# shematic.net
KiCad netlist of a schematic drawn in Altium Designer
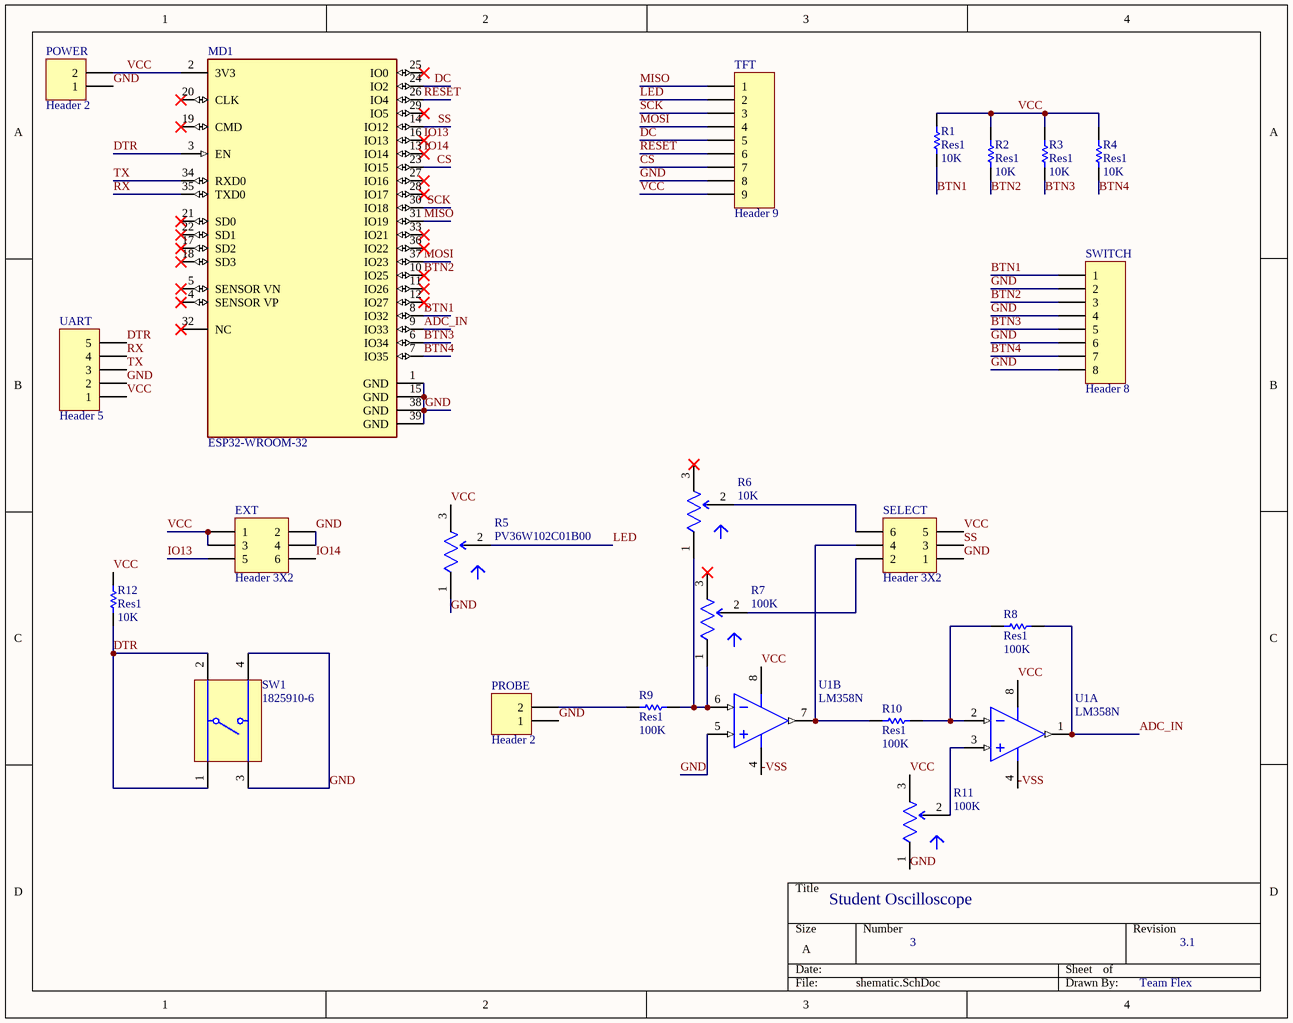
[diagram p0: shematic.SchDoc]

(export (version "E")
  (design (tool "Eeschema 10.0.6"))
  (components
    (comp (ref "EXT")
      (value "Header 3X2")
      (footprint "HDR2X3")
      (description "Header, 3-Pin, Dual row")
      (fields (field (name "PUBLISHER") "Altium Limited"))
      (libsource (lib "Miscellaneous Connectors") (part "Header 3X2"))
    )
    (comp (ref "MD1")
      (value "ESP32-WROOM-32")
      (footprint "FP-ESP32-WROOM-32-MFG")
      (description "RX TXRX MOD WIFI SURFACE MOUNT")
      (libsource (lib "Altium Content Vault") (part "ee866abf0b6c51247b7f5cdebf2f250"))
    )
    (comp (ref "POWER")
      (value "Header 2")
      (footprint "HDR1X2")
      (description "Header, 2-Pin")
      (fields (field (name "PUBLISHER") "Altium Limited"))
      (libsource (lib "Miscellaneous Connectors") (part "Header 2"))
    )
    (comp (ref "PROBE")
      (value "Header 2")
      (footprint "HDR1X2")
      (description "Header, 2-Pin")
      (fields (field (name "PUBLISHER") "Altium Limited"))
      (libsource (lib "Miscellaneous Connectors") (part "Header 2"))
    )
    (comp (ref "R1")
      (value "Res1")
      (footprint "AXIAL-0.3")
      (description "Resistor")
      (fields (field (name "ALTIUM_VALUE") "10K") (field (name "PUBLISHER") "Altium Limited"))
      (libsource (lib "Miscellaneous Devices") (part "Res1"))
    )
    (comp (ref "R2")
      (value "Res1")
      (footprint "AXIAL-0.3")
      (description "Resistor")
      (fields (field (name "ALTIUM_VALUE") "10K") (field (name "PUBLISHER") "Altium Limited"))
      (libsource (lib "Miscellaneous Devices") (part "Res1"))
    )
    (comp (ref "R3")
      (value "Res1")
      (footprint "AXIAL-0.3")
      (description "Resistor")
      (fields (field (name "ALTIUM_VALUE") "10K") (field (name "PUBLISHER") "Altium Limited"))
      (libsource (lib "Miscellaneous Devices") (part "Res1"))
    )
    (comp (ref "R4")
      (value "Res1")
      (footprint "AXIAL-0.3")
      (description "Resistor")
      (fields (field (name "ALTIUM_VALUE") "10K") (field (name "PUBLISHER") "Altium Limited"))
      (libsource (lib "Miscellaneous Devices") (part "Res1"))
    )
    (comp (ref "R5")
      (value "PV36W102C01B00")
      (footprint "FP-PV36W-MFG")
      (description "TRIMMER 1K OHM 0.5W PC PIN TOP")
      (fields
        (field (name "OCTOPART") "https://octopart.com/pv36w102c01b00-bourns-71612321")
        (field (name "TOLERANCE") "10%")
      )
      (libsource (lib "Altium Content Vault") (part "3b5a993e1b8b55ba5d1e0805a406c64"))
    )
    (comp (ref "R6")
      (value "10K")
      (footprint "FP-PV36W-MFG")
      (description "TRIMMER 1K OHM 0.5W PC PIN TOP")
      (fields
        (field (name "OCTOPART") "https://octopart.com/pv36w102c01b00-bourns-71612321")
        (field (name "MANUFACTURER PART NUMBER") "PV36W102C01B00")
      )
      (libsource (lib "Altium Content Vault") (part "3b5a993e1b8b55ba5d1e0805a406c64"))
    )
    (comp (ref "R7")
      (value "100K")
      (footprint "FP-PV36W-MFG")
      (description "TRIMMER 1K OHM 0.5W PC PIN TOP")
      (fields
        (field (name "OCTOPART") "https://octopart.com/pv36w102c01b00-bourns-71612321")
        (field (name "MANUFACTURER PART NUMBER") "PV36W102C01B00")
      )
      (libsource (lib "Altium Content Vault") (part "3b5a993e1b8b55ba5d1e0805a406c64"))
    )
    (comp (ref "R8")
      (value "Res1")
      (footprint "AXIAL-0.3")
      (description "Resistor")
      (fields (field (name "ALTIUM_VALUE") "100K") (field (name "PUBLISHER") "Altium Limited"))
      (libsource (lib "Miscellaneous Devices") (part "Res1"))
    )
    (comp (ref "R9")
      (value "Res1")
      (footprint "AXIAL-0.3")
      (description "Resistor")
      (fields (field (name "ALTIUM_VALUE") "100K") (field (name "PUBLISHER") "Altium Limited"))
      (libsource (lib "Miscellaneous Devices") (part "Res1"))
    )
    (comp (ref "R10")
      (value "Res1")
      (footprint "AXIAL-0.3")
      (description "Resistor")
      (fields (field (name "ALTIUM_VALUE") "100K") (field (name "PUBLISHER") "Altium Limited"))
      (libsource (lib "Miscellaneous Devices") (part "Res1"))
    )
    (comp (ref "R11")
      (value "100K")
      (footprint "FP-PV36W-MFG")
      (description "TRIMMER 1K OHM 0.5W PC PIN TOP")
      (fields
        (field (name "OCTOPART") "https://octopart.com/pv36w102c01b00-bourns-71612321")
        (field (name "MANUFACTURER PART NUMBER") "PV36W102C01B00")
      )
      (libsource (lib "Altium Content Vault") (part "3b5a993e1b8b55ba5d1e0805a406c64"))
    )
    (comp (ref "R12")
      (value "Res1")
      (footprint "AXIAL-0.3")
      (description "Resistor")
      (fields (field (name "ALTIUM_VALUE") "10K") (field (name "PUBLISHER") "Altium Limited"))
      (libsource (lib "Miscellaneous Devices") (part "Res1"))
    )
    (comp (ref "SELECT")
      (value "Header 3X2")
      (footprint "HDR2X3")
      (description "Header, 3-Pin, Dual row")
      (fields (field (name "PUBLISHER") "Altium Limited"))
      (libsource (lib "") (part "Header 3X2_1"))
    )
    (comp (ref "SW1")
      (value "1825910-6")
      (footprint "TECO-1825910-6_V")
      (description "Tact Switch, SPST-NO, 0.05 A, -35 to 85 degC, 4-Pin THD, RoHS, Bulk")
      (fields (field (name "MANUFACTURER") "TE Connectivity"))
      (libsource (lib "Altium Content Vault") (part "SW-SPST-4_A"))
    )
    (comp (ref "SWITCH")
      (value "Header 8")
      (footprint "HDR1X8")
      (description "Header, 8-Pin")
      (fields (field (name "PUBLISHER") "Altium Limited"))
      (libsource (lib "Miscellaneous Connectors") (part "Header 8"))
    )
    (comp (ref "TFT")
      (value "Header 9")
      (footprint "HDR1X9")
      (description "Header, 9-Pin")
      (fields (field (name "PUBLISHER") "Altium Limited"))
      (libsource (lib "Miscellaneous Connectors") (part "Header 9"))
    )
    (comp (ref "U1")
      (value "LM358N")
      (footprint "ONSC-PDIP-8-626-05_M")
      (description "Single Supply Dual Operational Amplifier, 3 to 32 V, 0 to 70 degC, 8-Pin PDIP, Tube")
      (fields (field (name "MANUFACTURER") "On Semiconductor"))
      (libsource (lib "Altium Content Vault") (part "ONSC-LM358_NCV2904-8"))
    )
    (comp (ref "UART")
      (value "Header 5")
      (footprint "HDR1X5")
      (description "Header, 5-Pin")
      (fields (field (name "PUBLISHER") "Altium Limited"))
      (libsource (lib "Miscellaneous Connectors") (part "Header 5"))
    )
  )
  (nets
    (net (code "1") (name "/-VSS") (class "Default")
      (node (ref "U1") (pin "4") (pinfunction "VEE/GND_4") (pintype "power_in"))
    )
    (net (code "2") (name "/ADC_IN") (class "Default")
      (node (ref "MD1") (pin "9") (pinfunction "IO33_9") (pintype "bidirectional"))
      (node (ref "R8") (pin "1") (pinfunction "1_1") (pintype "passive"))
      (node (ref "U1") (pin "1") (pinfunction "OUTA_1") (pintype "output"))
    )
    (net (code "3") (name "/BTN1") (class "Default")
      (node (ref "MD1") (pin "8") (pinfunction "IO32_8") (pintype "bidirectional"))
      (node (ref "R1") (pin "1") (pinfunction "1_1") (pintype "passive"))
      (node (ref "SWITCH") (pin "1") (pinfunction "1_1") (pintype "passive"))
    )
    (net (code "4") (name "/BTN2") (class "Default")
      (node (ref "MD1") (pin "10") (pinfunction "IO25_10") (pintype "bidirectional"))
      (node (ref "R2") (pin "1") (pinfunction "1_1") (pintype "passive"))
      (node (ref "SWITCH") (pin "3") (pinfunction "3_3") (pintype "passive"))
    )
    (net (code "5") (name "/BTN3") (class "Default")
      (node (ref "MD1") (pin "6") (pinfunction "IO34_6") (pintype "bidirectional"))
      (node (ref "R3") (pin "1") (pinfunction "1_1") (pintype "passive"))
      (node (ref "SWITCH") (pin "5") (pinfunction "5_5") (pintype "passive"))
    )
    (net (code "6") (name "/BTN4") (class "Default")
      (node (ref "MD1") (pin "7") (pinfunction "IO35_7") (pintype "bidirectional"))
      (node (ref "R4") (pin "1") (pinfunction "1_1") (pintype "passive"))
      (node (ref "SWITCH") (pin "7") (pinfunction "7_7") (pintype "passive"))
    )
    (net (code "7") (name "/CS") (class "Default")
      (node (ref "MD1") (pin "23") (pinfunction "IO15_23") (pintype "bidirectional"))
      (node (ref "TFT") (pin "7") (pinfunction "7_7") (pintype "passive"))
    )
    (net (code "8") (name "/DC") (class "Default")
      (node (ref "MD1") (pin "24") (pinfunction "IO2_24") (pintype "bidirectional"))
      (node (ref "TFT") (pin "5") (pinfunction "5_5") (pintype "passive"))
    )
    (net (code "9") (name "/DTR") (class "Default")
      (node (ref "MD1") (pin "3") (pinfunction "EN_3") (pintype "input"))
      (node (ref "R12") (pin "2") (pinfunction "2_2") (pintype "passive"))
      (node (ref "SW1") (pin "1") (pinfunction "1_1") (pintype "passive"))
      (node (ref "SW1") (pin "2") (pinfunction "2_2") (pintype "passive"))
      (node (ref "UART") (pin "5") (pinfunction "5_5") (pintype "passive"))
    )
    (net (code "10") (name "/GND") (class "Default")
      (node (ref "EXT") (pin "2") (pinfunction "2_2") (pintype "passive"))
      (node (ref "EXT") (pin "4") (pinfunction "4_4") (pintype "passive"))
      (node (ref "MD1") (pin "1") (pinfunction "GND_1") (pintype "power_in"))
      (node (ref "MD1") (pin "15") (pinfunction "GND_15") (pintype "power_in"))
      (node (ref "MD1") (pin "38") (pinfunction "GND_38") (pintype "power_in"))
      (node (ref "MD1") (pin "39") (pinfunction "GND_39") (pintype "power_in"))
      (node (ref "POWER") (pin "1") (pinfunction "1_1") (pintype "passive"))
      (node (ref "PROBE") (pin "1") (pinfunction "1_1") (pintype "passive"))
      (node (ref "R11") (pin "1") (pinfunction "1_1") (pintype "passive"))
      (node (ref "R5") (pin "1") (pinfunction "1_1") (pintype "passive"))
      (node (ref "SELECT") (pin "1") (pinfunction "1_1") (pintype "passive"))
      (node (ref "SW1") (pin "3") (pinfunction "3_3") (pintype "passive"))
      (node (ref "SW1") (pin "4") (pinfunction "4_4") (pintype "passive"))
      (node (ref "SWITCH") (pin "2") (pinfunction "2_2") (pintype "passive"))
      (node (ref "SWITCH") (pin "4") (pinfunction "4_4") (pintype "passive"))
      (node (ref "SWITCH") (pin "6") (pinfunction "6_6") (pintype "passive"))
      (node (ref "SWITCH") (pin "8") (pinfunction "8_8") (pintype "passive"))
      (node (ref "TFT") (pin "8") (pinfunction "8_8") (pintype "passive"))
      (node (ref "U1") (pin "5") (pinfunction "INB+_5") (pintype "input"))
      (node (ref "UART") (pin "2") (pinfunction "2_2") (pintype "passive"))
    )
    (net (code "11") (name "/IO13") (class "Default")
      (node (ref "EXT") (pin "5") (pinfunction "5_5") (pintype "passive"))
      (node (ref "MD1") (pin "16") (pinfunction "IO13_16") (pintype "bidirectional"))
    )
    (net (code "12") (name "/IO14") (class "Default")
      (node (ref "EXT") (pin "6") (pinfunction "6_6") (pintype "passive"))
      (node (ref "MD1") (pin "13") (pinfunction "IO14_13") (pintype "bidirectional"))
    )
    (net (code "13") (name "/LED") (class "Default")
      (node (ref "R5") (pin "2") (pinfunction "Wiper_2") (pintype "passive"))
      (node (ref "TFT") (pin "2") (pinfunction "2_2") (pintype "passive"))
    )
    (net (code "14") (name "/MISO") (class "Default")
      (node (ref "MD1") (pin "31") (pinfunction "IO19_31") (pintype "bidirectional"))
      (node (ref "TFT") (pin "1") (pinfunction "1_1") (pintype "passive"))
    )
    (net (code "15") (name "/MOSI") (class "Default")
      (node (ref "MD1") (pin "37") (pinfunction "IO23_37") (pintype "bidirectional"))
      (node (ref "TFT") (pin "4") (pinfunction "4_4") (pintype "passive"))
    )
    (net (code "16") (name "/RESET") (class "Default")
      (node (ref "MD1") (pin "26") (pinfunction "IO4_26") (pintype "bidirectional"))
      (node (ref "TFT") (pin "6") (pinfunction "6_6") (pintype "passive"))
    )
    (net (code "17") (name "/RX") (class "Default")
      (node (ref "MD1") (pin "35") (pinfunction "TXD0_35") (pintype "bidirectional"))
      (node (ref "UART") (pin "4") (pinfunction "4_4") (pintype "passive"))
    )
    (net (code "18") (name "/SCK") (class "Default")
      (node (ref "MD1") (pin "30") (pinfunction "IO18_30") (pintype "bidirectional"))
      (node (ref "TFT") (pin "3") (pinfunction "3_3") (pintype "passive"))
    )
    (net (code "19") (name "/SS") (class "Default")
      (node (ref "MD1") (pin "14") (pinfunction "IO12_14") (pintype "bidirectional"))
      (node (ref "SELECT") (pin "3") (pinfunction "3_3") (pintype "passive"))
    )
    (net (code "20") (name "/TX") (class "Default")
      (node (ref "MD1") (pin "34") (pinfunction "RXD0_34") (pintype "bidirectional"))
      (node (ref "UART") (pin "3") (pinfunction "3_3") (pintype "passive"))
    )
    (net (code "21") (name "/VCC") (class "Default")
      (node (ref "EXT") (pin "1") (pinfunction "1_1") (pintype "passive"))
      (node (ref "EXT") (pin "3") (pinfunction "3_3") (pintype "passive"))
      (node (ref "MD1") (pin "2") (pinfunction "3V3_2") (pintype "power_in"))
      (node (ref "POWER") (pin "2") (pinfunction "2_2") (pintype "passive"))
      (node (ref "R1") (pin "2") (pinfunction "2_2") (pintype "passive"))
      (node (ref "R11") (pin "3") (pinfunction "3_3") (pintype "passive"))
      (node (ref "R12") (pin "1") (pinfunction "1_1") (pintype "passive"))
      (node (ref "R2") (pin "2") (pinfunction "2_2") (pintype "passive"))
      (node (ref "R3") (pin "2") (pinfunction "2_2") (pintype "passive"))
      (node (ref "R4") (pin "2") (pinfunction "2_2") (pintype "passive"))
      (node (ref "R5") (pin "3") (pinfunction "3_3") (pintype "passive"))
      (node (ref "SELECT") (pin "5") (pinfunction "5_5") (pintype "passive"))
      (node (ref "TFT") (pin "9") (pinfunction "9_9") (pintype "passive"))
      (node (ref "U1") (pin "8") (pinfunction "VCC_8") (pintype "power_in"))
      (node (ref "UART") (pin "1") (pinfunction "1_1") (pintype "passive"))
    )
    (net (code "22") (name "Net-(PROBE-Pad2)") (class "Default")
      (node (ref "PROBE") (pin "2") (pinfunction "2_2") (pintype "passive"))
      (node (ref "R9") (pin "2") (pinfunction "2_2") (pintype "passive"))
    )
    (net (code "23") (name "Net-(R6-Wiper)") (class "Default")
      (node (ref "R6") (pin "2") (pinfunction "Wiper_2") (pintype "passive"))
      (node (ref "SELECT") (pin "6") (pinfunction "6_6") (pintype "passive"))
    )
    (net (code "24") (name "Net-(R7-Wiper)") (class "Default")
      (node (ref "R7") (pin "2") (pinfunction "Wiper_2") (pintype "passive"))
      (node (ref "SELECT") (pin "2") (pinfunction "2_2") (pintype "passive"))
    )
    (net (code "25") (name "Net-(R11-Wiper)") (class "Default")
      (node (ref "R11") (pin "2") (pinfunction "Wiper_2") (pintype "passive"))
      (node (ref "U1") (pin "3") (pinfunction "INA+_3") (pintype "input"))
    )
    (net (code "26") (name "Net-(U1A-INA-)") (class "Default")
      (node (ref "R10") (pin "1") (pinfunction "1_1") (pintype "passive"))
      (node (ref "R8") (pin "2") (pinfunction "2_2") (pintype "passive"))
      (node (ref "U1") (pin "2") (pinfunction "INA-_2") (pintype "input"))
    )
    (net (code "27") (name "Net-(U1B-INB-)") (class "Default")
      (node (ref "R6") (pin "1") (pinfunction "1_1") (pintype "passive"))
      (node (ref "R7") (pin "1") (pinfunction "1_1") (pintype "passive"))
      (node (ref "R9") (pin "1") (pinfunction "1_1") (pintype "passive"))
      (node (ref "U1") (pin "6") (pinfunction "INB-_6") (pintype "input"))
    )
    (net (code "28") (name "Net-(U1B-OUTB)") (class "Default")
      (node (ref "R10") (pin "2") (pinfunction "2_2") (pintype "passive"))
      (node (ref "SELECT") (pin "4") (pinfunction "4_4") (pintype "passive"))
      (node (ref "U1") (pin "7") (pinfunction "OUTB_7") (pintype "output"))
    )
    (net (code "29") (name "unconnected-(MD1-CLK-Pad20)") (class "Default")
      (node (ref "MD1") (pin "20") (pinfunction "CLK_20") (pintype "bidirectional+no_connect"))
    )
    (net (code "30") (name "unconnected-(MD1-CMD-Pad19)") (class "Default")
      (node (ref "MD1") (pin "19") (pinfunction "CMD_19") (pintype "bidirectional+no_connect"))
    )
    (net (code "31") (name "unconnected-(MD1-IO0-Pad25)") (class "Default")
      (node (ref "MD1") (pin "25") (pinfunction "IO0_25") (pintype "bidirectional+no_connect"))
    )
    (net (code "32") (name "unconnected-(MD1-IO5-Pad29)") (class "Default")
      (node (ref "MD1") (pin "29") (pinfunction "IO5_29") (pintype "bidirectional+no_connect"))
    )
    (net (code "33") (name "unconnected-(MD1-IO16-Pad27)") (class "Default")
      (node (ref "MD1") (pin "27") (pinfunction "IO16_27") (pintype "bidirectional+no_connect"))
    )
    (net (code "34") (name "unconnected-(MD1-IO17-Pad28)") (class "Default")
      (node (ref "MD1") (pin "28") (pinfunction "IO17_28") (pintype "bidirectional+no_connect"))
    )
    (net (code "35") (name "unconnected-(MD1-IO21-Pad33)") (class "Default")
      (node (ref "MD1") (pin "33") (pinfunction "IO21_33") (pintype "bidirectional+no_connect"))
    )
    (net (code "36") (name "unconnected-(MD1-IO22-Pad36)") (class "Default")
      (node (ref "MD1") (pin "36") (pinfunction "IO22_36") (pintype "bidirectional+no_connect"))
    )
    (net (code "37") (name "unconnected-(MD1-IO26-Pad11)") (class "Default")
      (node (ref "MD1") (pin "11") (pinfunction "IO26_11") (pintype "bidirectional+no_connect"))
    )
    (net (code "38") (name "unconnected-(MD1-IO27-Pad12)") (class "Default")
      (node (ref "MD1") (pin "12") (pinfunction "IO27_12") (pintype "bidirectional+no_connect"))
    )
    (net (code "39") (name "unconnected-(MD1-NC-Pad32)") (class "Default")
      (node (ref "MD1") (pin "32") (pinfunction "NC_32") (pintype "passive+no_connect"))
    )
    (net (code "40") (name "unconnected-(MD1-SD0-Pad21)") (class "Default")
      (node (ref "MD1") (pin "21") (pinfunction "SD0_21") (pintype "bidirectional+no_connect"))
    )
    (net (code "41") (name "unconnected-(MD1-SD1-Pad22)") (class "Default")
      (node (ref "MD1") (pin "22") (pinfunction "SD1_22") (pintype "bidirectional+no_connect"))
    )
    (net (code "42") (name "unconnected-(MD1-SD2-Pad17)") (class "Default")
      (node (ref "MD1") (pin "17") (pinfunction "SD2_17") (pintype "bidirectional+no_connect"))
    )
    (net (code "43") (name "unconnected-(MD1-SD3-Pad18)") (class "Default")
      (node (ref "MD1") (pin "18") (pinfunction "SD3_18") (pintype "bidirectional+no_connect"))
    )
    (net (code "44") (name "unconnected-(MD1-SENSOR_VN-Pad5)") (class "Default")
      (node (ref "MD1") (pin "5") (pinfunction "SENSOR_VN_5") (pintype "bidirectional+no_connect"))
    )
    (net (code "45") (name "unconnected-(MD1-SENSOR_VP-Pad4)") (class "Default")
      (node (ref "MD1") (pin "4") (pinfunction "SENSOR_VP_4") (pintype "bidirectional+no_connect"))
    )
    (net (code "46") (name "unconnected-(R6-Pad3)") (class "Default")
      (node (ref "R6") (pin "3") (pinfunction "3_3") (pintype "passive+no_connect"))
    )
    (net (code "47") (name "unconnected-(R7-Pad3)") (class "Default")
      (node (ref "R7") (pin "3") (pinfunction "3_3") (pintype "passive+no_connect"))
    )
  )
)
